# pcinterface-light.net
KiCad netlist of a schematic drawn in EAGLE
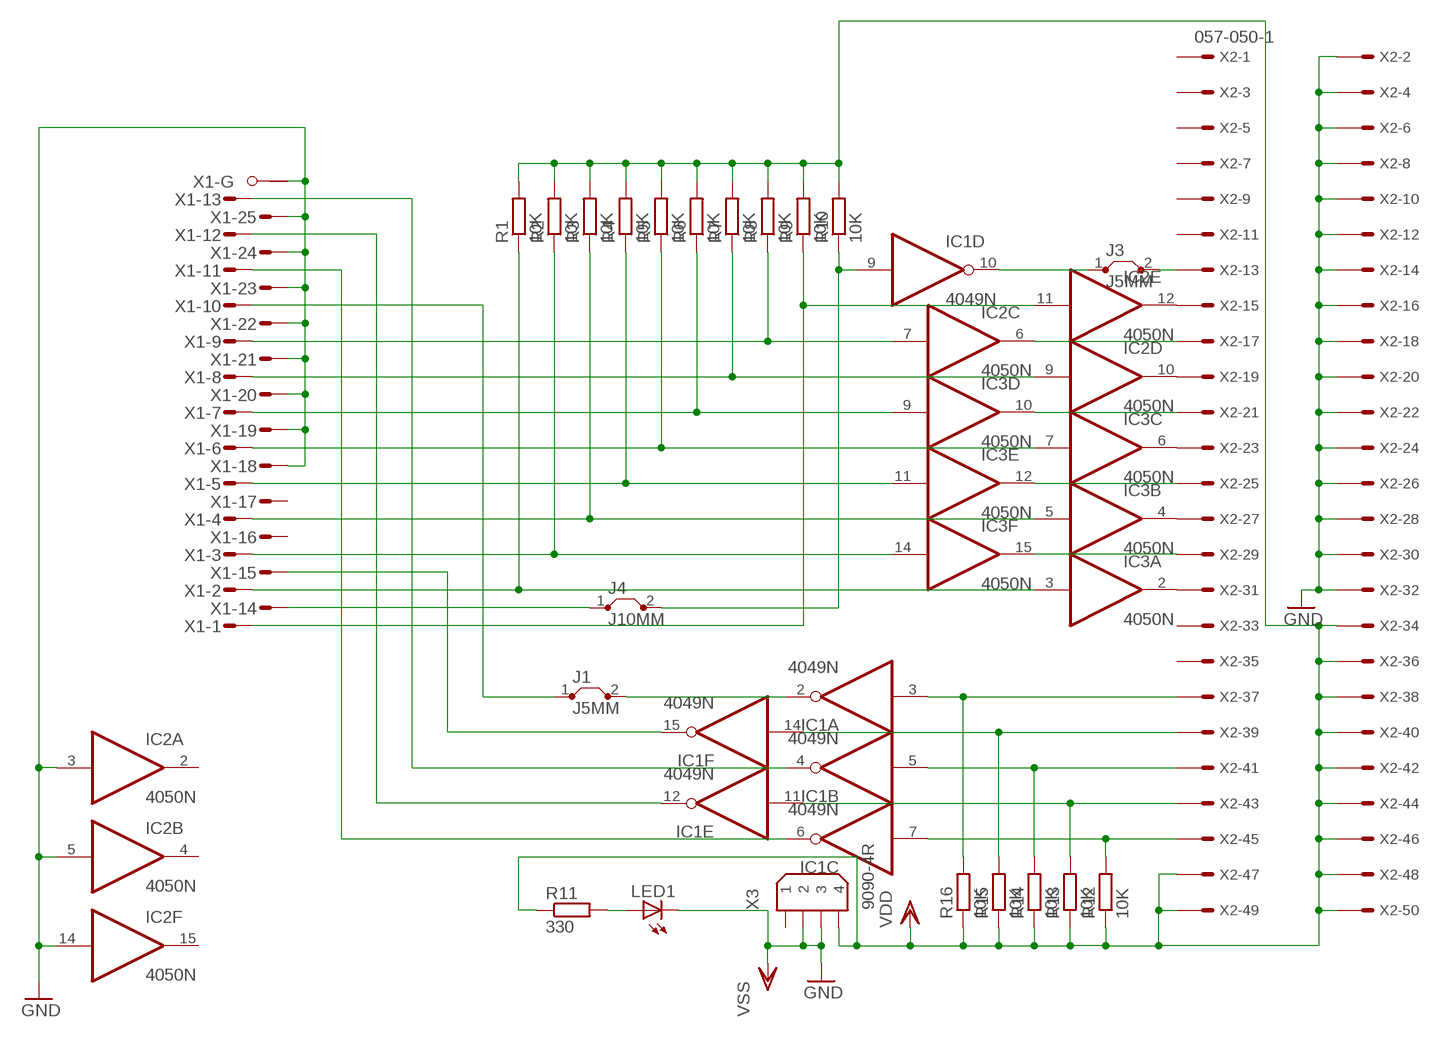
[diagram p0: schematic, sheet 1]

(export (version "E")
  (design (tool "Eeschema 10.0.6"))
  (components
    (comp (ref "IC1")
      (value "4049N")
      (footprint "eagle-import:DIL16")
      (libsource (lib "eagle-import") (part "4049N"))
    )
    (comp (ref "IC2")
      (value "4050N")
      (footprint "eagle-import:DIL16")
      (libsource (lib "eagle-import") (part "4050N"))
    )
    (comp (ref "IC3")
      (value "4050N")
      (footprint "eagle-import:DIL16")
      (libsource (lib "eagle-import") (part "4050N"))
    )
    (comp (ref "J1")
      (value "J5MM")
      (footprint "eagle-import:05")
      (libsource (lib "eagle-import") (part "J5MM"))
    )
    (comp (ref "J3")
      (value "J5MM")
      (footprint "eagle-import:05")
      (libsource (lib "eagle-import") (part "J5MM"))
    )
    (comp (ref "J4")
      (value "J10MM")
      (footprint "eagle-import:10")
      (libsource (lib "eagle-import") (part "J10MM"))
    )
    (comp (ref "LED1")
      (value "LED3MM")
      (footprint "eagle-import:LED3MM")
      (libsource (lib "eagle-import") (part "LED3MM"))
    )
    (comp (ref "R1")
      (value "10K")
      (footprint "eagle-import:0207_10")
      (libsource (lib "eagle-import") (part "R-EU_0207/10"))
    )
    (comp (ref "R2")
      (value "10K")
      (footprint "eagle-import:0207_10")
      (libsource (lib "eagle-import") (part "R-EU_0207/10"))
    )
    (comp (ref "R3")
      (value "10K")
      (footprint "eagle-import:0207_10")
      (libsource (lib "eagle-import") (part "R-EU_0207/10"))
    )
    (comp (ref "R4")
      (value "10K")
      (footprint "eagle-import:0207_10")
      (libsource (lib "eagle-import") (part "R-EU_0207/10"))
    )
    (comp (ref "R5")
      (value "10K")
      (footprint "eagle-import:0207_10")
      (libsource (lib "eagle-import") (part "R-EU_0207/10"))
    )
    (comp (ref "R6")
      (value "10K")
      (footprint "eagle-import:0207_10")
      (libsource (lib "eagle-import") (part "R-EU_0207/10"))
    )
    (comp (ref "R7")
      (value "10K")
      (footprint "eagle-import:0207_10")
      (libsource (lib "eagle-import") (part "R-EU_0207/10"))
    )
    (comp (ref "R8")
      (value "10K")
      (footprint "eagle-import:0207_10")
      (libsource (lib "eagle-import") (part "R-EU_0207/10"))
    )
    (comp (ref "R9")
      (value "10K")
      (footprint "eagle-import:0207_10")
      (libsource (lib "eagle-import") (part "R-EU_0207/10"))
    )
    (comp (ref "R10")
      (value "10K")
      (footprint "eagle-import:0207_10")
      (libsource (lib "eagle-import") (part "R-EU_0207/10"))
    )
    (comp (ref "R11")
      (value "330")
      (footprint "eagle-import:0207_10")
      (libsource (lib "eagle-import") (part "R-EU_0207/10"))
    )
    (comp (ref "R12")
      (value "10K")
      (footprint "eagle-import:0207_10")
      (libsource (lib "eagle-import") (part "R-EU_0207/10"))
    )
    (comp (ref "R13")
      (value "10K")
      (footprint "eagle-import:0207_10")
      (libsource (lib "eagle-import") (part "R-EU_0207/10"))
    )
    (comp (ref "R14")
      (value "10K")
      (footprint "eagle-import:0207_10")
      (libsource (lib "eagle-import") (part "R-EU_0207/10"))
    )
    (comp (ref "R15")
      (value "10K")
      (footprint "eagle-import:0207_10")
      (libsource (lib "eagle-import") (part "R-EU_0207/10"))
    )
    (comp (ref "R16")
      (value "10K")
      (footprint "eagle-import:0207_10")
      (libsource (lib "eagle-import") (part "R-EU_0207/10"))
    )
    (comp (ref "X1")
      (value "M25HPS")
      (footprint "eagle-import:M25HP")
      (libsource (lib "eagle-import") (part "M25HPS"))
    )
    (comp (ref "X2")
      (value "057-050-1")
      (footprint "eagle-import:057-050-1")
      (libsource (lib "eagle-import") (part "057-050-1"))
    )
    (comp (ref "X3")
      (value "9090-4R")
      (footprint "eagle-import:9090-4R")
      (libsource (lib "eagle-import") (part "9090-4R"))
    )
  )
  (nets
    (net (code "1") (name "GND") (class "Default")
      (node (ref "IC2") (pin "14") (pinfunction "I_14") (pintype "input"))
      (node (ref "IC2") (pin "3") (pinfunction "I_3") (pintype "input"))
      (node (ref "IC2") (pin "5") (pinfunction "I_5") (pintype "input"))
      (node (ref "LED1") (pin "K") (pinfunction "C_K") (pintype "passive"))
      (node (ref "X1") (pin "18") (pinfunction "M_18") (pintype "passive"))
      (node (ref "X1") (pin "19") (pinfunction "M_19") (pintype "passive"))
      (node (ref "X1") (pin "20") (pinfunction "M_20") (pintype "passive"))
      (node (ref "X1") (pin "21") (pinfunction "M_21") (pintype "passive"))
      (node (ref "X1") (pin "22") (pinfunction "M_22") (pintype "passive"))
      (node (ref "X1") (pin "23") (pinfunction "M_23") (pintype "passive"))
      (node (ref "X1") (pin "24") (pinfunction "M_24") (pintype "passive"))
      (node (ref "X1") (pin "25") (pinfunction "M_25") (pintype "passive"))
      (node (ref "X1") (pin "G1") (pinfunction "G1_G1") (pintype "passive"))
      (node (ref "X2") (pin "10") (pinfunction "S_10") (pintype "passive"))
      (node (ref "X2") (pin "12") (pinfunction "S_12") (pintype "passive"))
      (node (ref "X2") (pin "14") (pinfunction "S_14") (pintype "passive"))
      (node (ref "X2") (pin "16") (pinfunction "S_16") (pintype "passive"))
      (node (ref "X2") (pin "18") (pinfunction "S_18") (pintype "passive"))
      (node (ref "X2") (pin "2") (pinfunction "S_2") (pintype "passive"))
      (node (ref "X2") (pin "20") (pinfunction "S_20") (pintype "passive"))
      (node (ref "X2") (pin "22") (pinfunction "S_22") (pintype "passive"))
      (node (ref "X2") (pin "24") (pinfunction "S_24") (pintype "passive"))
      (node (ref "X2") (pin "26") (pinfunction "S_26") (pintype "passive"))
      (node (ref "X2") (pin "28") (pinfunction "S_28") (pintype "passive"))
      (node (ref "X2") (pin "30") (pinfunction "S_30") (pintype "passive"))
      (node (ref "X2") (pin "32") (pinfunction "S_32") (pintype "passive"))
      (node (ref "X2") (pin "4") (pinfunction "S_4") (pintype "passive"))
      (node (ref "X2") (pin "6") (pinfunction "S_6") (pintype "passive"))
      (node (ref "X2") (pin "8") (pinfunction "S_8") (pintype "passive"))
      (node (ref "X3") (pin "2") (pinfunction "2_2") (pintype "passive"))
      (node (ref "X3") (pin "3") (pinfunction "3_3") (pintype "passive"))
    )
    (net (code "2") (name "Net-(IC1A-I)") (class "Default")
      (node (ref "IC1") (pin "3") (pinfunction "I_3") (pintype "input"))
      (node (ref "R16") (pin "2") (pinfunction "2_2") (pintype "passive"))
      (node (ref "X2") (pin "37") (pinfunction "S_37") (pintype "passive"))
    )
    (net (code "3") (name "Net-(IC1A-O)") (class "Default")
      (node (ref "IC1") (pin "2") (pinfunction "O_2") (pintype "output"))
      (node (ref "J1") (pin "2") (pinfunction "2_2") (pintype "passive"))
    )
    (net (code "4") (name "Net-(IC1B-I)") (class "Default")
      (node (ref "IC1") (pin "5") (pinfunction "I_5") (pintype "input"))
      (node (ref "R14") (pin "2") (pinfunction "2_2") (pintype "passive"))
      (node (ref "X2") (pin "41") (pinfunction "S_41") (pintype "passive"))
    )
    (net (code "5") (name "Net-(IC1B-O)") (class "Default")
      (node (ref "IC1") (pin "4") (pinfunction "O_4") (pintype "output"))
      (node (ref "X1") (pin "13") (pinfunction "M_13") (pintype "passive"))
    )
    (net (code "6") (name "Net-(IC1C-I)") (class "Default")
      (node (ref "IC1") (pin "7") (pinfunction "I_7") (pintype "input"))
      (node (ref "R12") (pin "2") (pinfunction "2_2") (pintype "passive"))
      (node (ref "X2") (pin "45") (pinfunction "S_45") (pintype "passive"))
    )
    (net (code "7") (name "Net-(IC1C-O)") (class "Default")
      (node (ref "IC1") (pin "6") (pinfunction "O_6") (pintype "output"))
      (node (ref "X1") (pin "11") (pinfunction "M_11") (pintype "passive"))
    )
    (net (code "8") (name "Net-(IC1D-I)") (class "Default")
      (node (ref "IC1") (pin "9") (pinfunction "I_9") (pintype "input"))
      (node (ref "J4") (pin "2") (pinfunction "2_2") (pintype "passive"))
      (node (ref "R10") (pin "1") (pinfunction "1_1") (pintype "passive"))
    )
    (net (code "9") (name "Net-(IC1D-O)") (class "Default")
      (node (ref "IC1") (pin "10") (pinfunction "O_10") (pintype "output"))
      (node (ref "J3") (pin "1") (pinfunction "1_1") (pintype "passive"))
    )
    (net (code "10") (name "Net-(IC1E-I)") (class "Default")
      (node (ref "IC1") (pin "11") (pinfunction "I_11") (pintype "input"))
      (node (ref "R13") (pin "2") (pinfunction "2_2") (pintype "passive"))
      (node (ref "X2") (pin "43") (pinfunction "S_43") (pintype "passive"))
    )
    (net (code "11") (name "Net-(IC1E-O)") (class "Default")
      (node (ref "IC1") (pin "12") (pinfunction "O_12") (pintype "output"))
      (node (ref "X1") (pin "12") (pinfunction "M_12") (pintype "passive"))
    )
    (net (code "12") (name "Net-(IC1F-I)") (class "Default")
      (node (ref "IC1") (pin "14") (pinfunction "I_14") (pintype "input"))
      (node (ref "R15") (pin "2") (pinfunction "2_2") (pintype "passive"))
      (node (ref "X2") (pin "39") (pinfunction "S_39") (pintype "passive"))
    )
    (net (code "13") (name "Net-(IC1F-O)") (class "Default")
      (node (ref "IC1") (pin "15") (pinfunction "O_15") (pintype "output"))
      (node (ref "X1") (pin "15") (pinfunction "M_15") (pintype "passive"))
    )
    (net (code "14") (name "Net-(IC2C-I)") (class "Default")
      (node (ref "IC2") (pin "7") (pinfunction "I_7") (pintype "input"))
      (node (ref "R8") (pin "1") (pinfunction "1_1") (pintype "passive"))
      (node (ref "X1") (pin "9") (pinfunction "M_9") (pintype "passive"))
    )
    (net (code "15") (name "Net-(IC2C-O)") (class "Default")
      (node (ref "IC2") (pin "6") (pinfunction "O_6") (pintype "output"))
      (node (ref "X2") (pin "17") (pinfunction "S_17") (pintype "passive"))
    )
    (net (code "16") (name "Net-(IC2D-I)") (class "Default")
      (node (ref "IC2") (pin "9") (pinfunction "I_9") (pintype "input"))
      (node (ref "R7") (pin "1") (pinfunction "1_1") (pintype "passive"))
      (node (ref "X1") (pin "8") (pinfunction "M_8") (pintype "passive"))
    )
    (net (code "17") (name "Net-(IC2D-O)") (class "Default")
      (node (ref "IC2") (pin "10") (pinfunction "O_10") (pintype "output"))
      (node (ref "X2") (pin "19") (pinfunction "S_19") (pintype "passive"))
    )
    (net (code "18") (name "Net-(IC2E-I)") (class "Default")
      (node (ref "IC2") (pin "11") (pinfunction "I_11") (pintype "input"))
      (node (ref "R9") (pin "1") (pinfunction "1_1") (pintype "passive"))
      (node (ref "X1") (pin "1") (pinfunction "M_1") (pintype "passive"))
    )
    (net (code "19") (name "Net-(IC2E-O)") (class "Default")
      (node (ref "IC2") (pin "12") (pinfunction "O_12") (pintype "output"))
      (node (ref "X2") (pin "15") (pinfunction "S_15") (pintype "passive"))
    )
    (net (code "20") (name "Net-(IC3A-I)") (class "Default")
      (node (ref "IC3") (pin "3") (pinfunction "I_3") (pintype "input"))
      (node (ref "R1") (pin "1") (pinfunction "1_1") (pintype "passive"))
      (node (ref "X1") (pin "2") (pinfunction "M_2") (pintype "passive"))
    )
    (net (code "21") (name "Net-(IC3A-O)") (class "Default")
      (node (ref "IC3") (pin "2") (pinfunction "O_2") (pintype "output"))
      (node (ref "X2") (pin "31") (pinfunction "S_31") (pintype "passive"))
    )
    (net (code "22") (name "Net-(IC3B-I)") (class "Default")
      (node (ref "IC3") (pin "5") (pinfunction "I_5") (pintype "input"))
      (node (ref "R3") (pin "1") (pinfunction "1_1") (pintype "passive"))
      (node (ref "X1") (pin "4") (pinfunction "M_4") (pintype "passive"))
    )
    (net (code "23") (name "Net-(IC3B-O)") (class "Default")
      (node (ref "IC3") (pin "4") (pinfunction "O_4") (pintype "output"))
      (node (ref "X2") (pin "27") (pinfunction "S_27") (pintype "passive"))
    )
    (net (code "24") (name "Net-(IC3C-I)") (class "Default")
      (node (ref "IC3") (pin "7") (pinfunction "I_7") (pintype "input"))
      (node (ref "R5") (pin "1") (pinfunction "1_1") (pintype "passive"))
      (node (ref "X1") (pin "6") (pinfunction "M_6") (pintype "passive"))
    )
    (net (code "25") (name "Net-(IC3C-O)") (class "Default")
      (node (ref "IC3") (pin "6") (pinfunction "O_6") (pintype "output"))
      (node (ref "X2") (pin "23") (pinfunction "S_23") (pintype "passive"))
    )
    (net (code "26") (name "Net-(IC3D-I)") (class "Default")
      (node (ref "IC3") (pin "9") (pinfunction "I_9") (pintype "input"))
      (node (ref "R6") (pin "1") (pinfunction "1_1") (pintype "passive"))
      (node (ref "X1") (pin "7") (pinfunction "M_7") (pintype "passive"))
    )
    (net (code "27") (name "Net-(IC3D-O)") (class "Default")
      (node (ref "IC3") (pin "10") (pinfunction "O_10") (pintype "output"))
      (node (ref "X2") (pin "21") (pinfunction "S_21") (pintype "passive"))
    )
    (net (code "28") (name "Net-(IC3E-I)") (class "Default")
      (node (ref "IC3") (pin "11") (pinfunction "I_11") (pintype "input"))
      (node (ref "R4") (pin "1") (pinfunction "1_1") (pintype "passive"))
      (node (ref "X1") (pin "5") (pinfunction "M_5") (pintype "passive"))
    )
    (net (code "29") (name "Net-(IC3E-O)") (class "Default")
      (node (ref "IC3") (pin "12") (pinfunction "O_12") (pintype "output"))
      (node (ref "X2") (pin "25") (pinfunction "S_25") (pintype "passive"))
    )
    (net (code "30") (name "Net-(IC3F-I)") (class "Default")
      (node (ref "IC3") (pin "14") (pinfunction "I_14") (pintype "input"))
      (node (ref "R2") (pin "1") (pinfunction "1_1") (pintype "passive"))
      (node (ref "X1") (pin "3") (pinfunction "M_3") (pintype "passive"))
    )
    (net (code "31") (name "Net-(IC3F-O)") (class "Default")
      (node (ref "IC3") (pin "15") (pinfunction "O_15") (pintype "output"))
      (node (ref "X2") (pin "29") (pinfunction "S_29") (pintype "passive"))
    )
    (net (code "32") (name "Net-(LED1-PadA)") (class "Default")
      (node (ref "LED1") (pin "A") (pinfunction "A_A") (pintype "passive"))
      (node (ref "R11") (pin "2") (pinfunction "2_2") (pintype "passive"))
    )
    (net (code "33") (name "Net-(X1B-M)") (class "Default")
      (node (ref "J1") (pin "1") (pinfunction "1_1") (pintype "passive"))
      (node (ref "X1") (pin "10") (pinfunction "M_10") (pintype "passive"))
    )
    (net (code "34") (name "Net-(X1F-M)") (class "Default")
      (node (ref "J4") (pin "1") (pinfunction "1_1") (pintype "passive"))
      (node (ref "X1") (pin "14") (pinfunction "M_14") (pintype "passive"))
    )
    (net (code "35") (name "Net-(X2E-S)") (class "Default")
      (node (ref "J3") (pin "2") (pinfunction "2_2") (pintype "passive"))
      (node (ref "X2") (pin "13") (pinfunction "S_13") (pintype "passive"))
    )
    (net (code "36") (name "VDD") (class "Default")
      (node (ref "R1") (pin "2") (pinfunction "2_2") (pintype "passive"))
      (node (ref "R10") (pin "2") (pinfunction "2_2") (pintype "passive"))
      (node (ref "R11") (pin "1") (pinfunction "1_1") (pintype "passive"))
      (node (ref "R12") (pin "1") (pinfunction "1_1") (pintype "passive"))
      (node (ref "R13") (pin "1") (pinfunction "1_1") (pintype "passive"))
      (node (ref "R14") (pin "1") (pinfunction "1_1") (pintype "passive"))
      (node (ref "R15") (pin "1") (pinfunction "1_1") (pintype "passive"))
      (node (ref "R16") (pin "1") (pinfunction "1_1") (pintype "passive"))
      (node (ref "R2") (pin "2") (pinfunction "2_2") (pintype "passive"))
      (node (ref "R3") (pin "2") (pinfunction "2_2") (pintype "passive"))
      (node (ref "R4") (pin "2") (pinfunction "2_2") (pintype "passive"))
      (node (ref "R5") (pin "2") (pinfunction "2_2") (pintype "passive"))
      (node (ref "R6") (pin "2") (pinfunction "2_2") (pintype "passive"))
      (node (ref "R7") (pin "2") (pinfunction "2_2") (pintype "passive"))
      (node (ref "R8") (pin "2") (pinfunction "2_2") (pintype "passive"))
      (node (ref "R9") (pin "2") (pinfunction "2_2") (pintype "passive"))
      (node (ref "X2") (pin "34") (pinfunction "S_34") (pintype "passive"))
      (node (ref "X2") (pin "36") (pinfunction "S_36") (pintype "passive"))
      (node (ref "X2") (pin "38") (pinfunction "S_38") (pintype "passive"))
      (node (ref "X2") (pin "40") (pinfunction "S_40") (pintype "passive"))
      (node (ref "X2") (pin "42") (pinfunction "S_42") (pintype "passive"))
      (node (ref "X2") (pin "44") (pinfunction "S_44") (pintype "passive"))
      (node (ref "X2") (pin "46") (pinfunction "S_46") (pintype "passive"))
      (node (ref "X2") (pin "47") (pinfunction "S_47") (pintype "passive"))
      (node (ref "X2") (pin "48") (pinfunction "S_48") (pintype "passive"))
      (node (ref "X2") (pin "49") (pinfunction "S_49") (pintype "passive"))
      (node (ref "X2") (pin "50") (pinfunction "S_50") (pintype "passive"))
      (node (ref "X3") (pin "4") (pinfunction "4_4") (pintype "passive"))
    )
    (net (code "37") (name "unconnected-(IC2A-O-Pad2)") (class "Default")
      (node (ref "IC2") (pin "2") (pinfunction "O_2") (pintype "output"))
    )
    (net (code "38") (name "unconnected-(IC2B-O-Pad4)") (class "Default")
      (node (ref "IC2") (pin "4") (pinfunction "O_4") (pintype "output"))
    )
    (net (code "39") (name "unconnected-(IC2F-O-Pad15)") (class "Default")
      (node (ref "IC2") (pin "15") (pinfunction "O_15") (pintype "output"))
    )
    (net (code "40") (name "unconnected-(X1-PadG2)") (class "Default")
      (node (ref "X1") (pin "G2") (pinfunction "G2_G2") (pintype "passive"))
    )
    (net (code "41") (name "unconnected-(X1H-M-Pad16)") (class "Default")
      (node (ref "X1") (pin "16") (pinfunction "M_16") (pintype "passive"))
    )
    (net (code "42") (name "unconnected-(X1I-M-Pad17)") (class "Default")
      (node (ref "X1") (pin "17") (pinfunction "M_17") (pintype "passive"))
    )
    (net (code "43") (name "unconnected-(X2A-S-Pad1)") (class "Default")
      (node (ref "X2") (pin "1") (pinfunction "S_1") (pintype "passive"))
    )
    (net (code "44") (name "unconnected-(X2AA-S-Pad33)") (class "Default")
      (node (ref "X2") (pin "33") (pinfunction "S_33") (pintype "passive"))
    )
    (net (code "45") (name "unconnected-(X2AC-S-Pad35)") (class "Default")
      (node (ref "X2") (pin "35") (pinfunction "S_35") (pintype "passive"))
    )
    (net (code "46") (name "unconnected-(X2AS-S-Pad5)") (class "Default")
      (node (ref "X2") (pin "5") (pinfunction "S_5") (pintype "passive"))
    )
    (net (code "47") (name "unconnected-(X2AV-S-Pad7)") (class "Default")
      (node (ref "X2") (pin "7") (pinfunction "S_7") (pintype "passive"))
    )
    (net (code "48") (name "unconnected-(X2AX-S-Pad9)") (class "Default")
      (node (ref "X2") (pin "9") (pinfunction "S_9") (pintype "passive"))
    )
    (net (code "49") (name "unconnected-(X2C-S-Pad11)") (class "Default")
      (node (ref "X2") (pin "11") (pinfunction "S_11") (pintype "passive"))
    )
    (net (code "50") (name "unconnected-(X2W-S-Pad3)") (class "Default")
      (node (ref "X2") (pin "3") (pinfunction "S_3") (pintype "passive"))
    )
    (net (code "51") (name "unconnected-(X3-Pad1)") (class "Default")
      (node (ref "X3") (pin "1") (pinfunction "1_1") (pintype "passive"))
    )
  )
)
